# Xblast_Jafar-SE_-_EasyEDA_-_Schematic_Ex.net
KiCad netlist of a schematic drawn in EasyEDA
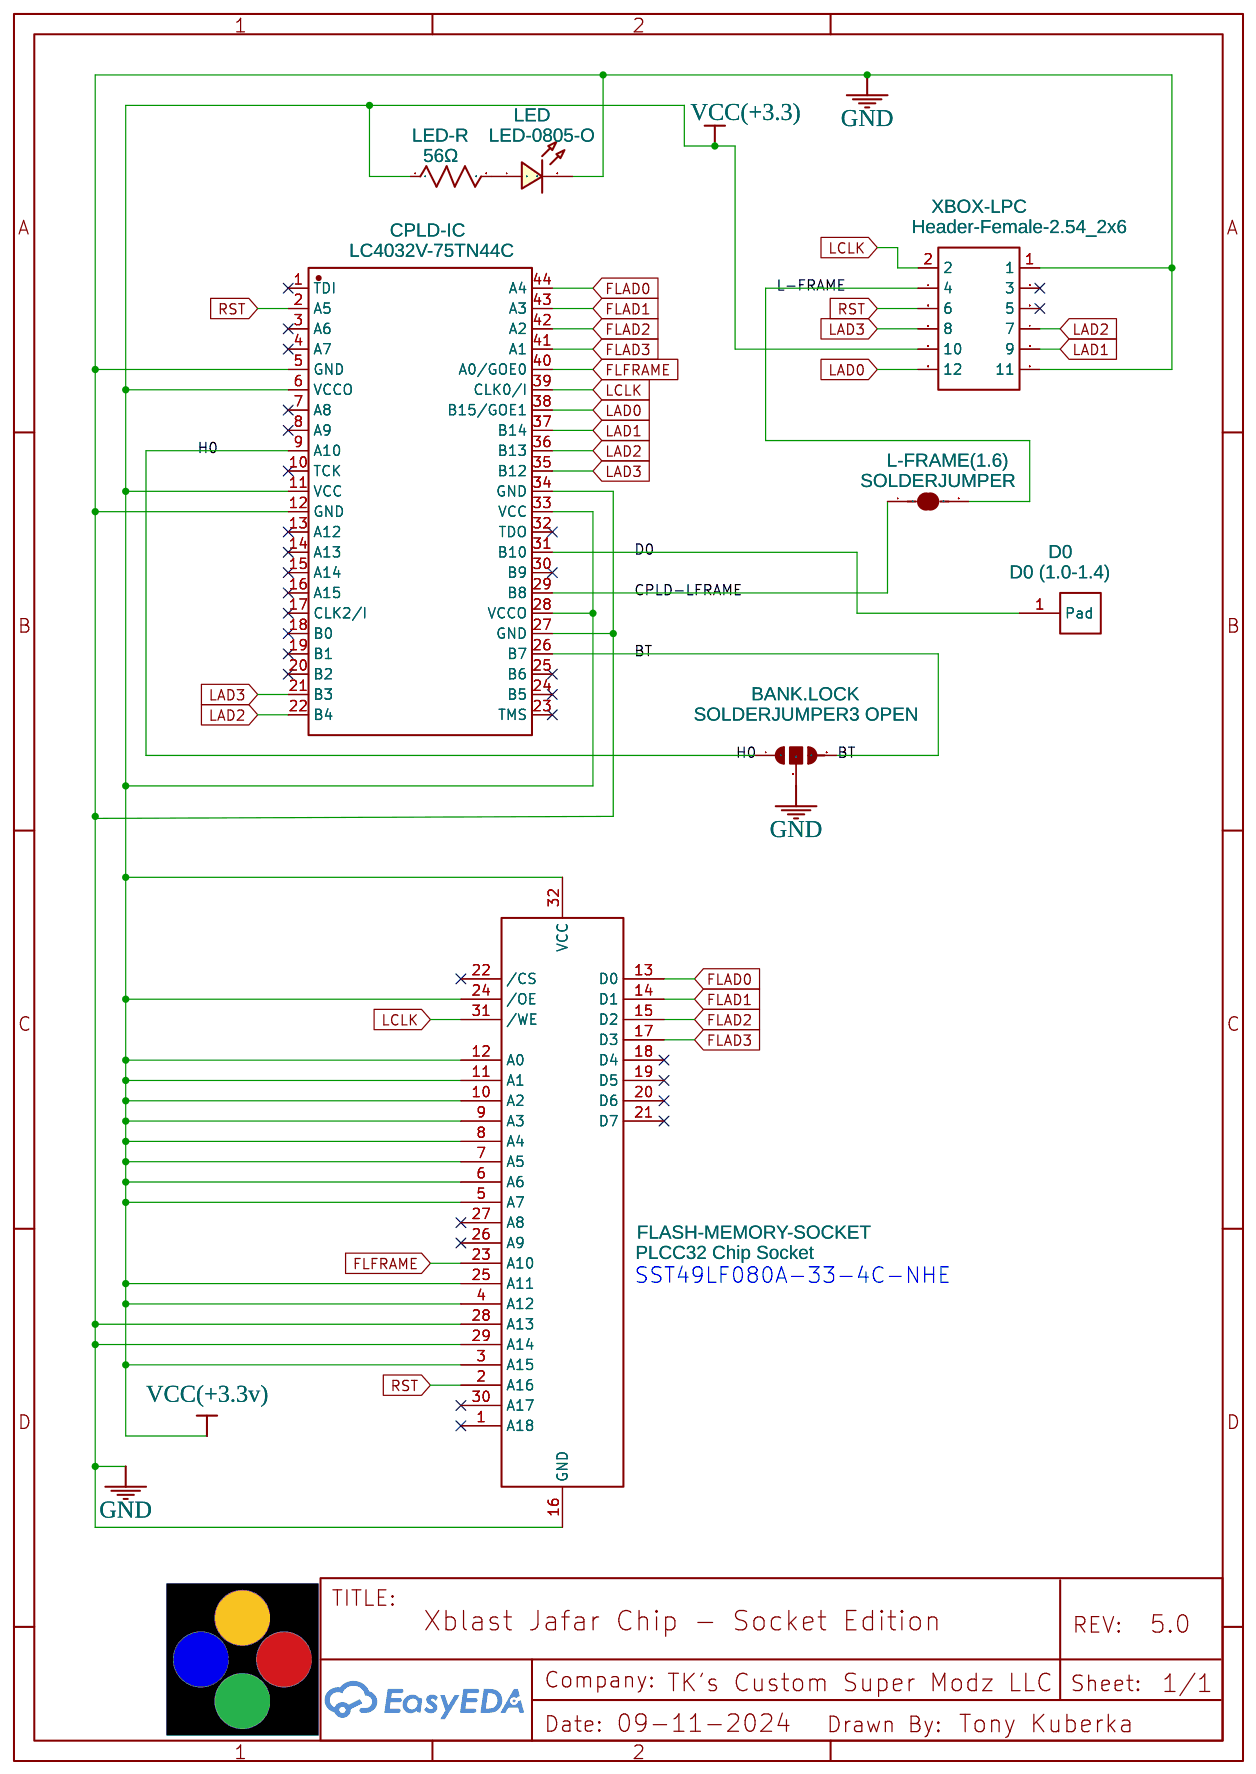
[diagram p0: schematic sheet]

(export (version "E")
  (design (tool "Eeschema 10.0.6"))
  (components
    (comp (ref "BANK.LOCK") (value "SOLDERJUMPER3 OPEN") (libsource (lib "") (part "SOLDERJUMPER3 OPEN")))
    (comp (ref "CPLD-IC")
      (value "LC4032V-75TN44C")
      (fields (field (name "Manufacturer") "LATTICE(莱迪思)"))
      (libsource (lib "") (part "LC4032V-75TN44C"))
    )
    (comp (ref "D0") (value "D0 (1.0-1.4)") (libsource (lib "") (part "SOLDER PAD")))
    (comp (ref "FLASH-MEMORY-SOCKET")
      (value "PLCC32 Chip Socket")
      (fields
        (field (name "Manufacturer Part") "SST39VF040-70-4C-NHE")
        (field (name "Manufacturer") "Microchip Technology")
      )
      (libsource (lib "") (part "SST39VF040-70-4C-NHE"))
    )
    (comp (ref "L-FRAME(1.6)") (value "SOLDERJUMPER") (libsource (lib "") (part "SOLDERJUMPER-OLDNC2")))
    (comp (ref "LED")
      (value "LED-0805-O")
      (fields
        (field (name "Manufacturer Part") "SZYY0805O")
        (field (name "Manufacturer") "Yongyu Photoelectric")
      )
      (libsource (lib "") (part "LED-0805-ORANGE"))
    )
    (comp (ref "LED-R") (value "56Ω") (libsource (lib "") (part "R_0805_US")))
    (comp (ref "XBOX-LPC")
      (value "Header-Female-2.54_2x6")
      (fields (field (name "Manufacturer Part") "2.54-2*6P母") (field (name "Manufacturer") "BOOMELE(博穆精密)"))
      (libsource (lib "") (part "Header-Female-2.54_2x6"))
    )
  )
  (nets
    (net (code "1") (name "/BT") (class "Default")
      (node (ref "BANK.LOCK") (pin "3") (pinfunction "3_3") (pintype "unspecified"))
      (node (ref "CPLD-IC") (pin "26") (pinfunction "B7_26") (pintype "unspecified"))
    )
    (net (code "2") (name "/CPLD-LFRAME") (class "Default")
      (node (ref "CPLD-IC") (pin "29") (pinfunction "B8_29") (pintype "unspecified"))
      (node (ref "L-FRAME(1.6)") (pin "1") (pinfunction "1_1") (pintype "unspecified"))
    )
    (net (code "3") (name "/D0") (class "Default")
      (node (ref "CPLD-IC") (pin "31") (pinfunction "B10_31") (pintype "unspecified"))
      (node (ref "D0") (pin "1") (pinfunction "Pad_1") (pintype "unspecified"))
    )
    (net (code "4") (name "/H0") (class "Default")
      (node (ref "BANK.LOCK") (pin "1") (pinfunction "1_1") (pintype "unspecified"))
      (node (ref "CPLD-IC") (pin "9") (pinfunction "A10_9") (pintype "unspecified"))
    )
    (net (code "5") (name "/L-FRAME") (class "Default")
      (node (ref "L-FRAME(1.6)") (pin "2") (pinfunction "2_2") (pintype "unspecified"))
      (node (ref "XBOX-LPC") (pin "4") (pinfunction "4_4") (pintype "input"))
    )
    (net (code "6") (name "FLAD0") (class "Default")
      (node (ref "CPLD-IC") (pin "44") (pinfunction "A4_44") (pintype "unspecified"))
      (node (ref "FLASH-MEMORY-SOCKET") (pin "13") (pinfunction "D0_13") (pintype "unspecified"))
    )
    (net (code "7") (name "FLAD1") (class "Default")
      (node (ref "CPLD-IC") (pin "43") (pinfunction "A3_43") (pintype "unspecified"))
      (node (ref "FLASH-MEMORY-SOCKET") (pin "14") (pinfunction "D1_14") (pintype "unspecified"))
    )
    (net (code "8") (name "FLAD2") (class "Default")
      (node (ref "CPLD-IC") (pin "42") (pinfunction "A2_42") (pintype "unspecified"))
      (node (ref "FLASH-MEMORY-SOCKET") (pin "15") (pinfunction "D2_15") (pintype "unspecified"))
    )
    (net (code "9") (name "FLAD3") (class "Default")
      (node (ref "CPLD-IC") (pin "41") (pinfunction "A1_41") (pintype "unspecified"))
      (node (ref "FLASH-MEMORY-SOCKET") (pin "17") (pinfunction "D3_17") (pintype "unspecified"))
    )
    (net (code "10") (name "FLFRAME") (class "Default")
      (node (ref "CPLD-IC") (pin "40") (pinfunction "A0/GOE0_40") (pintype "unspecified"))
      (node (ref "FLASH-MEMORY-SOCKET") (pin "23") (pinfunction "A10_23") (pintype "unspecified"))
    )
    (net (code "11") (name "GND") (class "Default")
      (node (ref "BANK.LOCK") (pin "2") (pinfunction "2_2") (pintype "unspecified"))
      (node (ref "CPLD-IC") (pin "12") (pinfunction "GND_12") (pintype "unspecified"))
      (node (ref "CPLD-IC") (pin "27") (pinfunction "GND_27") (pintype "unspecified"))
      (node (ref "CPLD-IC") (pin "34") (pinfunction "GND_34") (pintype "unspecified"))
      (node (ref "CPLD-IC") (pin "5") (pinfunction "GND_5") (pintype "unspecified"))
      (node (ref "FLASH-MEMORY-SOCKET") (pin "16") (pinfunction "GND_16") (pintype "unspecified"))
      (node (ref "FLASH-MEMORY-SOCKET") (pin "28") (pinfunction "A13_28") (pintype "unspecified"))
      (node (ref "FLASH-MEMORY-SOCKET") (pin "29") (pinfunction "A14_29") (pintype "unspecified"))
      (node (ref "LED") (pin "2") (pinfunction "2_2") (pintype "unspecified"))
      (node (ref "XBOX-LPC") (pin "1") (pinfunction "1_1") (pintype "input"))
      (node (ref "XBOX-LPC") (pin "11") (pinfunction "11_11") (pintype "input"))
    )
    (net (code "12") (name "LAD0") (class "Default")
      (node (ref "CPLD-IC") (pin "38") (pinfunction "B15/GOE1_38") (pintype "unspecified"))
      (node (ref "XBOX-LPC") (pin "12") (pinfunction "12_12") (pintype "input"))
    )
    (net (code "13") (name "LAD1") (class "Default")
      (node (ref "CPLD-IC") (pin "37") (pinfunction "B14_37") (pintype "unspecified"))
      (node (ref "XBOX-LPC") (pin "9") (pinfunction "9_9") (pintype "input"))
    )
    (net (code "14") (name "LAD2") (class "Default")
      (node (ref "CPLD-IC") (pin "22") (pinfunction "B4_22") (pintype "unspecified"))
      (node (ref "CPLD-IC") (pin "36") (pinfunction "B13_36") (pintype "unspecified"))
      (node (ref "XBOX-LPC") (pin "7") (pinfunction "7_7") (pintype "input"))
    )
    (net (code "15") (name "LAD3") (class "Default")
      (node (ref "CPLD-IC") (pin "21") (pinfunction "B3_21") (pintype "unspecified"))
      (node (ref "CPLD-IC") (pin "35") (pinfunction "B12_35") (pintype "unspecified"))
      (node (ref "XBOX-LPC") (pin "8") (pinfunction "8_8") (pintype "input"))
    )
    (net (code "16") (name "LCLK") (class "Default")
      (node (ref "CPLD-IC") (pin "39") (pinfunction "CLK0/I_39") (pintype "unspecified"))
      (node (ref "FLASH-MEMORY-SOCKET") (pin "31") (pinfunction "/WE_31") (pintype "unspecified"))
      (node (ref "XBOX-LPC") (pin "2") (pinfunction "2_2") (pintype "input"))
    )
    (net (code "17") (name "Net-(LED-Pad1)") (class "Default")
      (node (ref "LED") (pin "1") (pinfunction "1_1") (pintype "unspecified"))
      (node (ref "LED-R") (pin "2") (pinfunction "2_2") (pintype "unspecified"))
    )
    (net (code "18") (name "RST") (class "Default")
      (node (ref "CPLD-IC") (pin "2") (pinfunction "A5_2") (pintype "unspecified"))
      (node (ref "FLASH-MEMORY-SOCKET") (pin "2") (pinfunction "A16_2") (pintype "unspecified"))
      (node (ref "XBOX-LPC") (pin "6") (pinfunction "6_6") (pintype "input"))
    )
    (net (code "19") (name "VCC(+3.3)") (class "Default")
      (node (ref "CPLD-IC") (pin "11") (pinfunction "VCC_11") (pintype "unspecified"))
      (node (ref "CPLD-IC") (pin "28") (pinfunction "VCCO_28") (pintype "unspecified"))
      (node (ref "CPLD-IC") (pin "33") (pinfunction "VCC_33") (pintype "unspecified"))
      (node (ref "CPLD-IC") (pin "6") (pinfunction "VCCO_6") (pintype "unspecified"))
      (node (ref "FLASH-MEMORY-SOCKET") (pin "10") (pinfunction "A2_10") (pintype "unspecified"))
      (node (ref "FLASH-MEMORY-SOCKET") (pin "11") (pinfunction "A1_11") (pintype "unspecified"))
      (node (ref "FLASH-MEMORY-SOCKET") (pin "12") (pinfunction "A0_12") (pintype "unspecified"))
      (node (ref "FLASH-MEMORY-SOCKET") (pin "24") (pinfunction "/OE_24") (pintype "unspecified"))
      (node (ref "FLASH-MEMORY-SOCKET") (pin "25") (pinfunction "A11_25") (pintype "unspecified"))
      (node (ref "FLASH-MEMORY-SOCKET") (pin "3") (pinfunction "A15_3") (pintype "unspecified"))
      (node (ref "FLASH-MEMORY-SOCKET") (pin "32") (pinfunction "VCC_32") (pintype "unspecified"))
      (node (ref "FLASH-MEMORY-SOCKET") (pin "4") (pinfunction "A12_4") (pintype "unspecified"))
      (node (ref "FLASH-MEMORY-SOCKET") (pin "5") (pinfunction "A7_5") (pintype "unspecified"))
      (node (ref "FLASH-MEMORY-SOCKET") (pin "6") (pinfunction "A6_6") (pintype "unspecified"))
      (node (ref "FLASH-MEMORY-SOCKET") (pin "7") (pinfunction "A5_7") (pintype "unspecified"))
      (node (ref "FLASH-MEMORY-SOCKET") (pin "8") (pinfunction "A4_8") (pintype "unspecified"))
      (node (ref "FLASH-MEMORY-SOCKET") (pin "9") (pinfunction "A3_9") (pintype "unspecified"))
      (node (ref "LED-R") (pin "1") (pinfunction "1_1") (pintype "unspecified"))
      (node (ref "XBOX-LPC") (pin "10") (pinfunction "10_10") (pintype "input"))
    )
    (net (code "20") (name "unconnected-(CPLD-IC-A6-Pad3)") (class "Default")
      (node (ref "CPLD-IC") (pin "3") (pinfunction "A6_3") (pintype "unspecified+no_connect"))
    )
    (net (code "21") (name "unconnected-(CPLD-IC-A7-Pad4)") (class "Default")
      (node (ref "CPLD-IC") (pin "4") (pinfunction "A7_4") (pintype "unspecified+no_connect"))
    )
    (net (code "22") (name "unconnected-(CPLD-IC-A8-Pad7)") (class "Default")
      (node (ref "CPLD-IC") (pin "7") (pinfunction "A8_7") (pintype "unspecified+no_connect"))
    )
    (net (code "23") (name "unconnected-(CPLD-IC-A9-Pad8)") (class "Default")
      (node (ref "CPLD-IC") (pin "8") (pinfunction "A9_8") (pintype "unspecified+no_connect"))
    )
    (net (code "24") (name "unconnected-(CPLD-IC-A12-Pad13)") (class "Default")
      (node (ref "CPLD-IC") (pin "13") (pinfunction "A12_13") (pintype "unspecified+no_connect"))
    )
    (net (code "25") (name "unconnected-(CPLD-IC-A13-Pad14)") (class "Default")
      (node (ref "CPLD-IC") (pin "14") (pinfunction "A13_14") (pintype "unspecified+no_connect"))
    )
    (net (code "26") (name "unconnected-(CPLD-IC-A14-Pad15)") (class "Default")
      (node (ref "CPLD-IC") (pin "15") (pinfunction "A14_15") (pintype "unspecified+no_connect"))
    )
    (net (code "27") (name "unconnected-(CPLD-IC-A15-Pad16)") (class "Default")
      (node (ref "CPLD-IC") (pin "16") (pinfunction "A15_16") (pintype "unspecified+no_connect"))
    )
    (net (code "28") (name "unconnected-(CPLD-IC-B0-Pad18)") (class "Default")
      (node (ref "CPLD-IC") (pin "18") (pinfunction "B0_18") (pintype "unspecified+no_connect"))
    )
    (net (code "29") (name "unconnected-(CPLD-IC-B1-Pad19)") (class "Default")
      (node (ref "CPLD-IC") (pin "19") (pinfunction "B1_19") (pintype "unspecified+no_connect"))
    )
    (net (code "30") (name "unconnected-(CPLD-IC-B2-Pad20)") (class "Default")
      (node (ref "CPLD-IC") (pin "20") (pinfunction "B2_20") (pintype "unspecified+no_connect"))
    )
    (net (code "31") (name "unconnected-(CPLD-IC-B5-Pad24)") (class "Default")
      (node (ref "CPLD-IC") (pin "24") (pinfunction "B5_24") (pintype "unspecified+no_connect"))
    )
    (net (code "32") (name "unconnected-(CPLD-IC-B6-Pad25)") (class "Default")
      (node (ref "CPLD-IC") (pin "25") (pinfunction "B6_25") (pintype "unspecified+no_connect"))
    )
    (net (code "33") (name "unconnected-(CPLD-IC-B9-Pad30)") (class "Default")
      (node (ref "CPLD-IC") (pin "30") (pinfunction "B9_30") (pintype "unspecified+no_connect"))
    )
    (net (code "34") (name "unconnected-(CPLD-IC-CLK2{slash}I-Pad17)") (class "Default")
      (node (ref "CPLD-IC") (pin "17") (pinfunction "CLK2/I_17") (pintype "unspecified+no_connect"))
    )
    (net (code "35") (name "unconnected-(CPLD-IC-TCK-Pad10)") (class "Default")
      (node (ref "CPLD-IC") (pin "10") (pinfunction "TCK_10") (pintype "unspecified+no_connect"))
    )
    (net (code "36") (name "unconnected-(CPLD-IC-TDI-Pad1)") (class "Default")
      (node (ref "CPLD-IC") (pin "1") (pinfunction "TDI_1") (pintype "unspecified+no_connect"))
    )
    (net (code "37") (name "unconnected-(CPLD-IC-TDO-Pad32)") (class "Default")
      (node (ref "CPLD-IC") (pin "32") (pinfunction "TDO_32") (pintype "unspecified+no_connect"))
    )
    (net (code "38") (name "unconnected-(CPLD-IC-TMS-Pad23)") (class "Default")
      (node (ref "CPLD-IC") (pin "23") (pinfunction "TMS_23") (pintype "unspecified+no_connect"))
    )
    (net (code "39") (name "unconnected-(FLASH-MEMORY-SOCKET-A8-Pad27)") (class "Default")
      (node (ref "FLASH-MEMORY-SOCKET") (pin "27") (pinfunction "A8_27") (pintype "unspecified+no_connect"))
    )
    (net (code "40") (name "unconnected-(FLASH-MEMORY-SOCKET-A9-Pad26)") (class "Default")
      (node (ref "FLASH-MEMORY-SOCKET") (pin "26") (pinfunction "A9_26") (pintype "unspecified+no_connect"))
    )
    (net (code "41") (name "unconnected-(FLASH-MEMORY-SOCKET-A17-Pad30)") (class "Default")
      (node (ref "FLASH-MEMORY-SOCKET") (pin "30") (pinfunction "A17_30") (pintype "unspecified+no_connect"))
    )
    (net (code "42") (name "unconnected-(FLASH-MEMORY-SOCKET-A18-Pad1)") (class "Default")
      (node (ref "FLASH-MEMORY-SOCKET") (pin "1") (pinfunction "A18_1") (pintype "unspecified+no_connect"))
    )
    (net (code "43") (name "unconnected-(FLASH-MEMORY-SOCKET-D4-Pad18)") (class "Default")
      (node (ref "FLASH-MEMORY-SOCKET") (pin "18") (pinfunction "D4_18") (pintype "unspecified+no_connect"))
    )
    (net (code "44") (name "unconnected-(FLASH-MEMORY-SOCKET-D5-Pad19)") (class "Default")
      (node (ref "FLASH-MEMORY-SOCKET") (pin "19") (pinfunction "D5_19") (pintype "unspecified+no_connect"))
    )
    (net (code "45") (name "unconnected-(FLASH-MEMORY-SOCKET-D6-Pad20)") (class "Default")
      (node (ref "FLASH-MEMORY-SOCKET") (pin "20") (pinfunction "D6_20") (pintype "unspecified+no_connect"))
    )
    (net (code "46") (name "unconnected-(FLASH-MEMORY-SOCKET-D7-Pad21)") (class "Default")
      (node (ref "FLASH-MEMORY-SOCKET") (pin "21") (pinfunction "D7_21") (pintype "unspecified+no_connect"))
    )
    (net (code "47") (name "unconnected-(FLASH-MEMORY-SOCKET-{slash}CS-Pad22)") (class "Default")
      (node (ref "FLASH-MEMORY-SOCKET") (pin "22") (pinfunction "/CS_22") (pintype "unspecified+no_connect"))
    )
    (net (code "48") (name "unconnected-(XBOX-LPC-Pad3)") (class "Default")
      (node (ref "XBOX-LPC") (pin "3") (pinfunction "3_3") (pintype "input+no_connect"))
    )
    (net (code "49") (name "unconnected-(XBOX-LPC-Pad5)") (class "Default")
      (node (ref "XBOX-LPC") (pin "5") (pinfunction "5_5") (pintype "input+no_connect"))
    )
  )
)
